# Nusbio_TestExtension_01.net
KiCad netlist of a schematic drawn in EAGLE
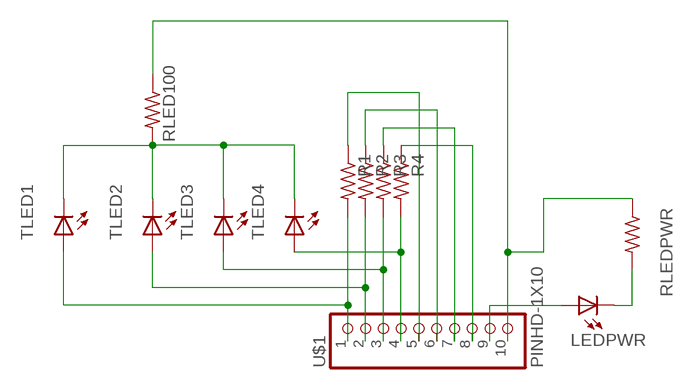
[diagram p0: schematic, sheet 1]

(export (version "E")
  (design (tool "Eeschema 10.0.6"))
  (components
    (comp (ref "LEDPWR")
      (value "LEDCHIPLED_0805")
      (footprint "eagle-import:CHIPLED_0805")
      (libsource (lib "eagle-import") (part "LEDCHIPLED_0805"))
    )
    (comp (ref "R1")
      (value "R-US_R0805")
      (footprint "eagle-import:R0805")
      (libsource (lib "eagle-import") (part "R-US_R0805"))
    )
    (comp (ref "R2")
      (value "R-US_R0805")
      (footprint "eagle-import:R0805")
      (libsource (lib "eagle-import") (part "R-US_R0805"))
    )
    (comp (ref "R3")
      (value "R-US_R0805")
      (footprint "eagle-import:R0805")
      (libsource (lib "eagle-import") (part "R-US_R0805"))
    )
    (comp (ref "R4")
      (value "R-US_R0805")
      (footprint "eagle-import:R0805")
      (libsource (lib "eagle-import") (part "R-US_R0805"))
    )
    (comp (ref "RLED100")
      (value "R-US_R0805")
      (footprint "eagle-import:R0805")
      (libsource (lib "eagle-import") (part "R-US_R0805"))
    )
    (comp (ref "RLEDPWR")
      (value "R-US_R0805")
      (footprint "eagle-import:R0805")
      (libsource (lib "eagle-import") (part "R-US_R0805"))
    )
    (comp (ref "TLED1")
      (value "LEDCHIPLED_0805")
      (footprint "eagle-import:CHIPLED_0805")
      (libsource (lib "eagle-import") (part "LEDCHIPLED_0805"))
    )
    (comp (ref "TLED2")
      (value "LEDCHIPLED_0805")
      (footprint "eagle-import:CHIPLED_0805")
      (libsource (lib "eagle-import") (part "LEDCHIPLED_0805"))
    )
    (comp (ref "TLED3")
      (value "LEDCHIPLED_0805")
      (footprint "eagle-import:CHIPLED_0805")
      (libsource (lib "eagle-import") (part "LEDCHIPLED_0805"))
    )
    (comp (ref "TLED4")
      (value "LEDCHIPLED_0805")
      (footprint "eagle-import:CHIPLED_0805")
      (libsource (lib "eagle-import") (part "LEDCHIPLED_0805"))
    )
    (comp (ref "U$1")
      (value "PINHD-1X10")
      (footprint "eagle-import:1X10-BIG")
      (libsource (lib "eagle-import") (part "PINHD-1X10"))
    )
  )
  (nets
    (net (code "1") (name "Net-(LEDPWR-PadA)") (class "Default")
      (node (ref "LEDPWR") (pin "A") (pinfunction "A_A") (pintype "passive"))
      (node (ref "U$1") (pin "9") (pinfunction "9_9") (pintype "passive"))
    )
    (net (code "2") (name "Net-(LEDPWR-PadC)") (class "Default")
      (node (ref "LEDPWR") (pin "C") (pinfunction "C_C") (pintype "passive"))
      (node (ref "RLEDPWR") (pin "2") (pinfunction "2_2") (pintype "passive"))
    )
    (net (code "3") (name "Net-(R1-Pad1)") (class "Default")
      (node (ref "R1") (pin "1") (pinfunction "1_1") (pintype "passive"))
      (node (ref "U$1") (pin "5") (pinfunction "5_5") (pintype "passive"))
    )
    (net (code "4") (name "Net-(R1-Pad2)") (class "Default")
      (node (ref "R1") (pin "2") (pinfunction "2_2") (pintype "passive"))
      (node (ref "TLED1") (pin "A") (pinfunction "A_A") (pintype "passive"))
      (node (ref "U$1") (pin "1") (pinfunction "1_1") (pintype "passive"))
    )
    (net (code "5") (name "Net-(R2-Pad1)") (class "Default")
      (node (ref "R2") (pin "1") (pinfunction "1_1") (pintype "passive"))
      (node (ref "U$1") (pin "6") (pinfunction "6_6") (pintype "passive"))
    )
    (net (code "6") (name "Net-(R2-Pad2)") (class "Default")
      (node (ref "R2") (pin "2") (pinfunction "2_2") (pintype "passive"))
      (node (ref "TLED2") (pin "A") (pinfunction "A_A") (pintype "passive"))
      (node (ref "U$1") (pin "2") (pinfunction "2_2") (pintype "passive"))
    )
    (net (code "7") (name "Net-(R3-Pad1)") (class "Default")
      (node (ref "R3") (pin "1") (pinfunction "1_1") (pintype "passive"))
      (node (ref "U$1") (pin "7") (pinfunction "7_7") (pintype "passive"))
    )
    (net (code "8") (name "Net-(R3-Pad2)") (class "Default")
      (node (ref "R3") (pin "2") (pinfunction "2_2") (pintype "passive"))
      (node (ref "TLED3") (pin "A") (pinfunction "A_A") (pintype "passive"))
      (node (ref "U$1") (pin "3") (pinfunction "3_3") (pintype "passive"))
    )
    (net (code "9") (name "Net-(R4-Pad1)") (class "Default")
      (node (ref "R4") (pin "1") (pinfunction "1_1") (pintype "passive"))
      (node (ref "U$1") (pin "8") (pinfunction "8_8") (pintype "passive"))
    )
    (net (code "10") (name "Net-(R4-Pad2)") (class "Default")
      (node (ref "R4") (pin "2") (pinfunction "2_2") (pintype "passive"))
      (node (ref "TLED4") (pin "A") (pinfunction "A_A") (pintype "passive"))
      (node (ref "U$1") (pin "4") (pinfunction "4_4") (pintype "passive"))
    )
    (net (code "11") (name "Net-(RLED100-Pad1)") (class "Default")
      (node (ref "RLED100") (pin "1") (pinfunction "1_1") (pintype "passive"))
      (node (ref "RLEDPWR") (pin "1") (pinfunction "1_1") (pintype "passive"))
      (node (ref "U$1") (pin "10") (pinfunction "10_10") (pintype "passive"))
    )
    (net (code "12") (name "Net-(RLED100-Pad2)") (class "Default")
      (node (ref "RLED100") (pin "2") (pinfunction "2_2") (pintype "passive"))
      (node (ref "TLED1") (pin "C") (pinfunction "C_C") (pintype "passive"))
      (node (ref "TLED2") (pin "C") (pinfunction "C_C") (pintype "passive"))
      (node (ref "TLED3") (pin "C") (pinfunction "C_C") (pintype "passive"))
      (node (ref "TLED4") (pin "C") (pinfunction "C_C") (pintype "passive"))
    )
  )
)
